# NTC.net
KiCad netlist of a schematic drawn in Altium Designer
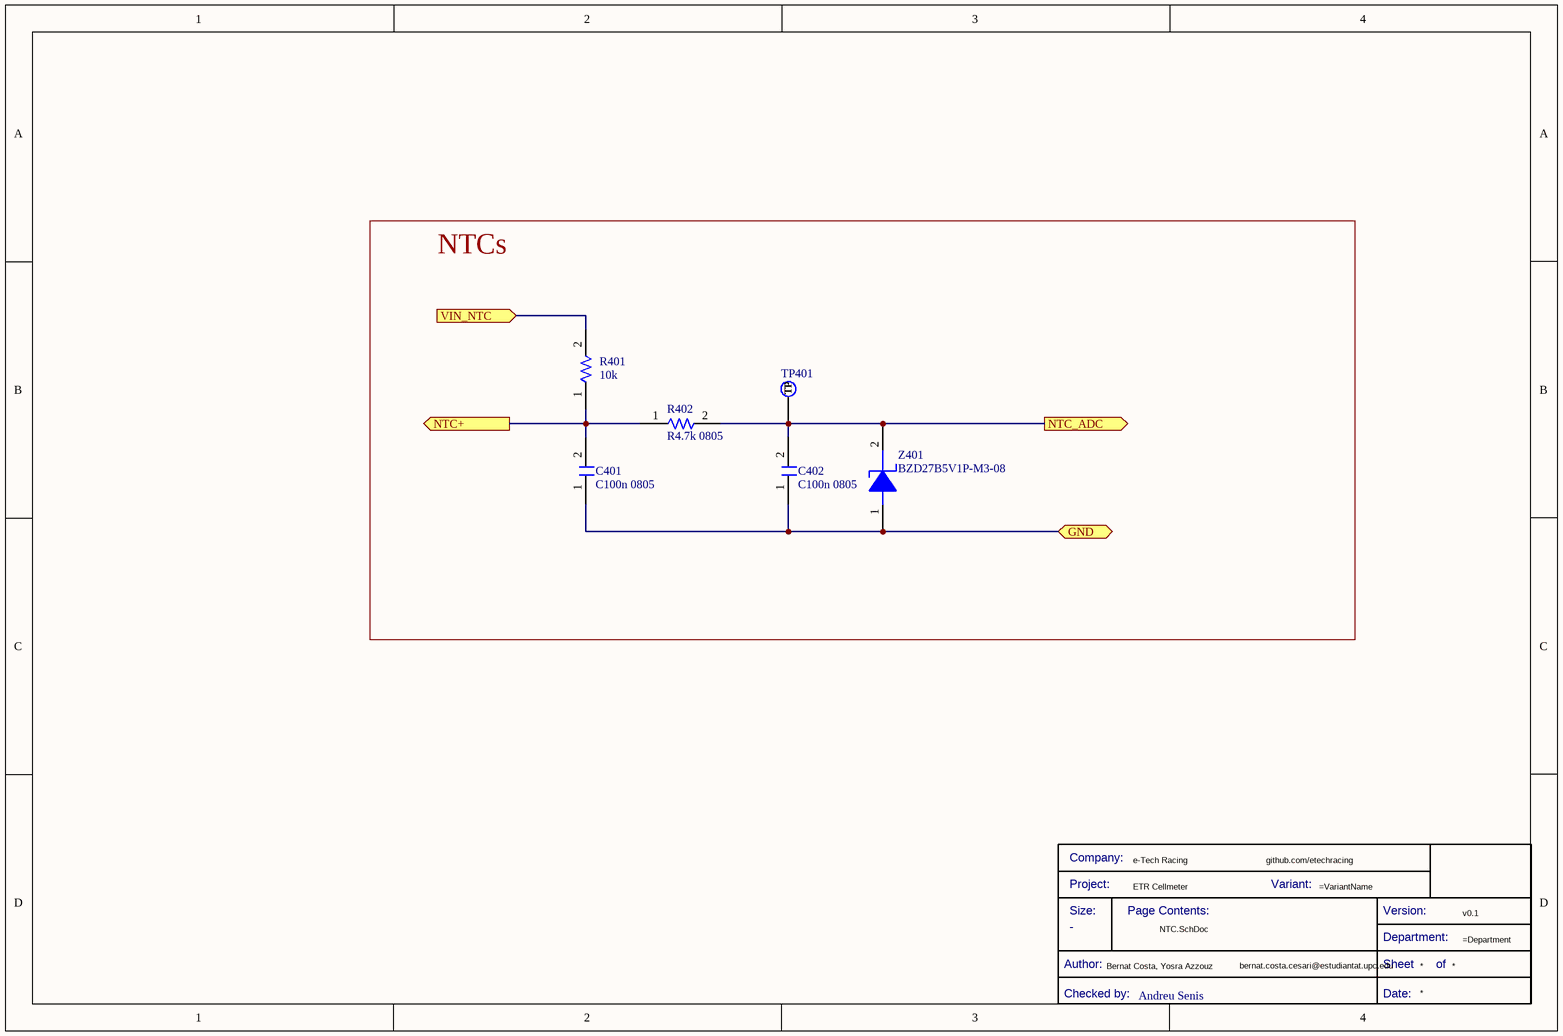
[diagram p0: NTC.SchDoc]

(export (version "E")
  (design (tool "Eeschema 10.0.6"))
  (components
    (comp (ref "*")
      (value "Title Block_template")
      (description "Standard Title Block")
      (fields
        (field (name "SIZE") "-")
        (field (name ".CREATOR") "GP")
        (field (name ".PCBCHECK") "GP")
        (field (name ".SCHCHECK") "GP")
      )
      (libsource (lib "e-Tech_Racing") (part "Title Block_template"))
    )
    (comp (ref "C401")
      (value "C100n 0805")
      (footprint "C0805FNPC-R")
      (description "Cap, 0.1ΜF, 50V, 10%, X7R, 0805")
      (fields (field (name "TOLERANCE") "10%") (field (name ".CREATOR") "DR"))
      (libsource (lib "EMEA- E-Tech Racing- I'Escola d'Enginyeria de Barcelona Est") (part "C100p-50V-0805FNPC-C0G/NP0"))
    )
    (comp (ref "C402")
      (value "C100n 0805")
      (footprint "C0805FNPC-R")
      (description "Cap, 0.1ΜF, 50V, 10%, X7R, 0805")
      (fields (field (name "TOLERANCE") "10%") (field (name ".CREATOR") "DR"))
      (libsource (lib "EMEA- E-Tech Racing- I'Escola d'Enginyeria de Barcelona Est") (part "C100p-50V-0805FNPC-C0G/NP0"))
    )
    (comp (ref "R401")
      (value "10k")
      (footprint "R0805FTK")
      (fields
        (field (name "TOLERANCE") "5%")
        (field (name "Comment") "R10k-0805FTK")
        (field (name ".CREATOR") "DR")
      )
      (libsource (lib "EMEA- E-Tech Racing- I'Escola d'Enginyeria de Barcelona Est") (part "R9.09K-1206FTK"))
    )
    (comp (ref "R402")
      (value "R4.7k 0805")
      (footprint "R0805FTK")
      (description "Res Thick Film 0805 4.7K Ohm 5% 1/8W ±200ppm/°C Molded SMD SMD Paper Tape on Plastic Reel")
      (fields (field (name "TOLERANCE") "5%") (field (name ".CREATOR") "DR"))
      (libsource (lib "EMEA- E-Tech Racing- I'Escola d'Enginyeria de Barcelona Est") (part "MPT35A1R0F"))
    )
    (comp (ref "TP401")
      (value "TestPoint")
      (footprint "TestPoint")
      (description "Test Point 1x1 mm")
      (fields (field (name ".SCHCHECK") "GP") (field (name ".CREATOR") "GP") (field (name ".PCBCHECK") "GP"))
      (libsource (lib "EMEA- E-Tech Racing- I'Escola d'Enginyeria de Barcelona Est") (part "TestPoint"))
    )
    (comp (ref "Z401")
      (value "BZD27B5V1P-M3-08")
      (footprint "SODFL370X108-2N")
      (description "Zener Diode, 5.1V V(Z), 2%, 0.8W, Silicon, Unidirectional, DO-219AB")
      (libsource (lib "EMEA- E-Tech Racing- I'Escola d'Enginyeria de Barcelona Est") (part "BZD27B5V1P-M3-08-Symbol-1"))
    )
  )
  (nets
    (net (code "1") (name "/GND") (class "Default")
      (node (ref "C401") (pin "1") (pinfunction "1_1") (pintype "passive"))
      (node (ref "C402") (pin "1") (pinfunction "1_1") (pintype "passive"))
      (node (ref "Z401") (pin "1") (pinfunction "1_1") (pintype "passive"))
    )
    (net (code "2") (name "/NTC+") (class "Default")
      (node (ref "C401") (pin "2") (pinfunction "2_2") (pintype "passive"))
      (node (ref "R401") (pin "1") (pinfunction "1_1") (pintype "passive"))
      (node (ref "R402") (pin "1") (pinfunction "1_1") (pintype "passive"))
    )
    (net (code "3") (name "/NTC_ADC") (class "Default")
      (node (ref "C402") (pin "2") (pinfunction "2_2") (pintype "passive"))
      (node (ref "R402") (pin "2") (pinfunction "2_2") (pintype "passive"))
      (node (ref "TP401") (pin "1") (pinfunction "TP_1") (pintype "passive"))
      (node (ref "Z401") (pin "2") (pinfunction "2_2") (pintype "passive"))
    )
    (net (code "4") (name "/VIN_NTC") (class "Default")
      (node (ref "R401") (pin "2") (pinfunction "2_2") (pintype "passive"))
    )
  )
)
